# schematic.net
KiCad netlist of a schematic drawn in EasyEDA
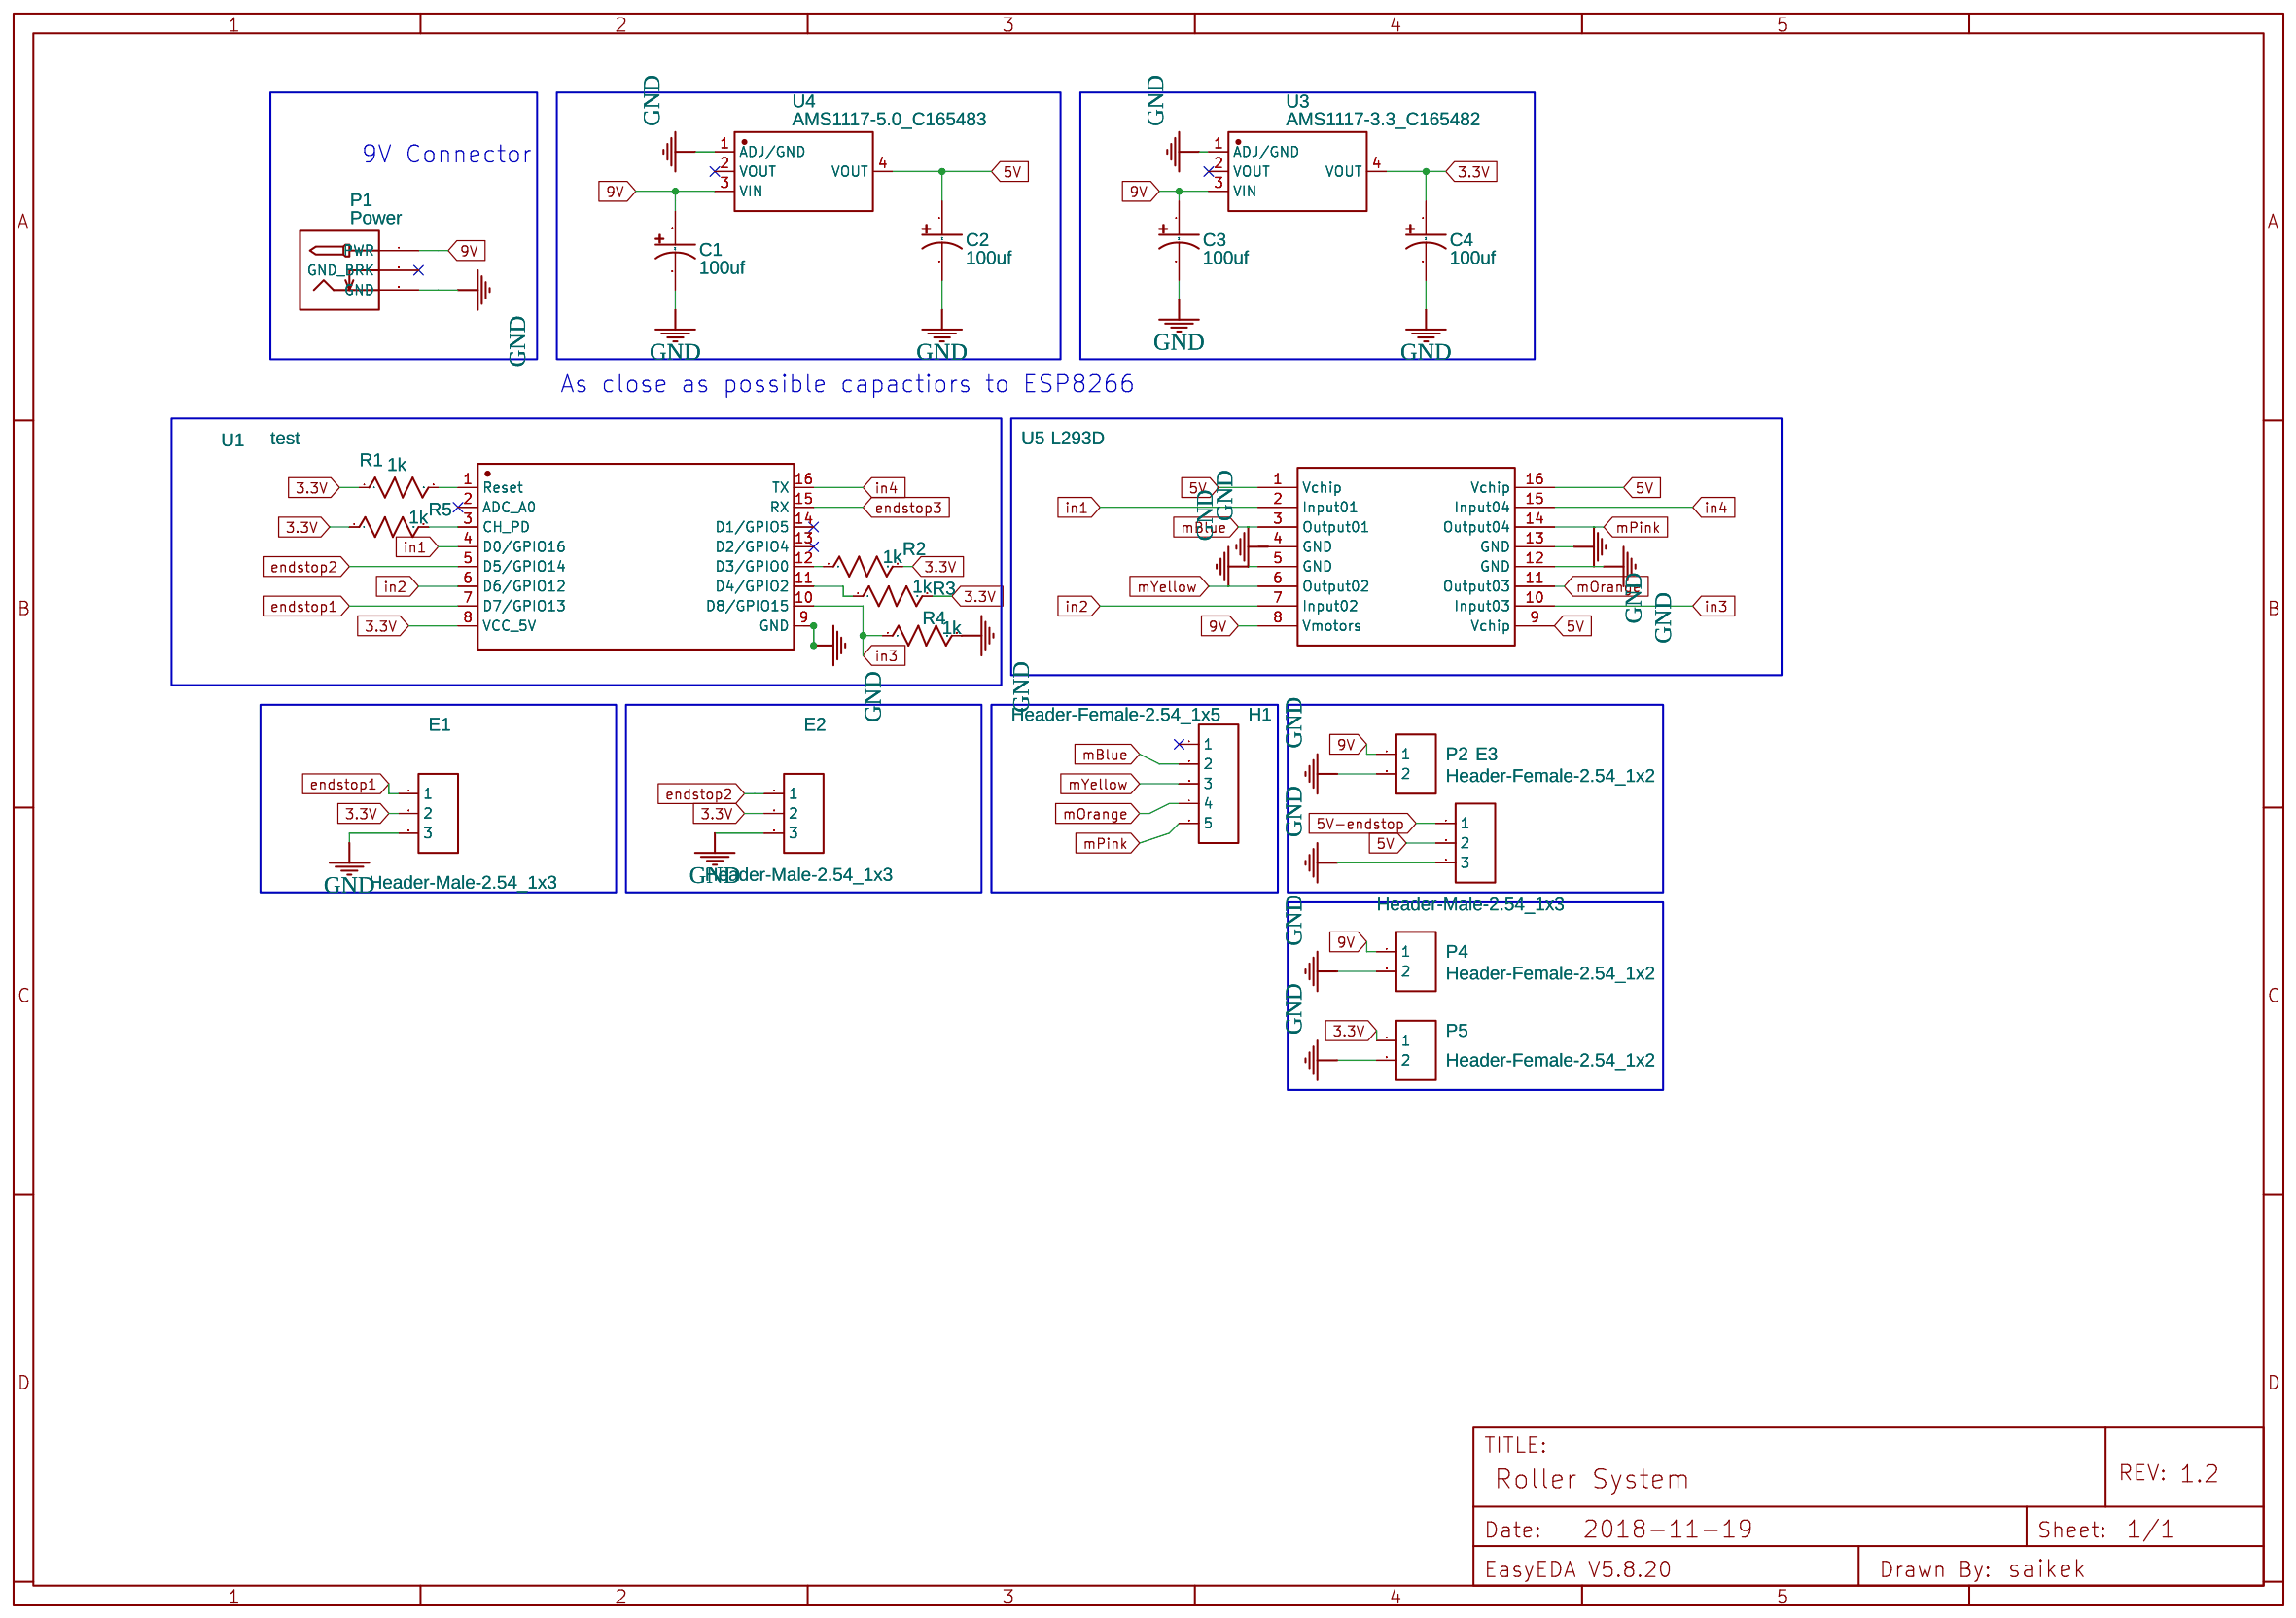
[diagram p0: schematic sheet]

(export (version "E")
  (design (tool "Eeschema 10.0.6"))
  (components
    (comp (ref "C1")
      (value "100uf")
      (fields (field (name "BOM_Manufacturer Part") "?"))
      (libsource (lib "") (part "Cap_Electrolytic(TH)_D3.0XF1.5_US"))
    )
    (comp (ref "C2")
      (value "100uf")
      (fields (field (name "BOM_Manufacturer Part") "?"))
      (libsource (lib "") (part "Cap_Electrolytic(TH)_D3.0XF1.5_US"))
    )
    (comp (ref "C3")
      (value "100uf")
      (fields (field (name "BOM_Manufacturer Part") "?"))
      (libsource (lib "") (part "Cap_Electrolytic(TH)_D3.0XF1.5_US"))
    )
    (comp (ref "C4")
      (value "100uf")
      (fields (field (name "BOM_Manufacturer Part") "?"))
      (libsource (lib "") (part "Cap_Electrolytic(TH)_D3.0XF1.5_US"))
    )
    (comp (ref "E1")
      (value "Header-Male-2.54_1x3")
      (fields
        (field (name "BOM_Manufacturer Part") "Header2.54mm 1*3P")
        (field (name "BOM_Supplier Part") "C49257")
      )
      (libsource (lib "") (part "Unknown_205_405"))
    )
    (comp (ref "E2")
      (value "Header-Male-2.54_1x3")
      (fields
        (field (name "BOM_Manufacturer Part") "Header2.54mm 1*3P")
        (field (name "BOM_Supplier Part") "C49257")
      )
      (libsource (lib "") (part "Unknown_390_405"))
    )
    (comp (ref "E3")
      (value "Header-Male-2.54_1x3")
      (fields
        (field (name "BOM_Manufacturer Part") "Header2.54mm 1*3P")
        (field (name "BOM_Supplier Part") "C49257")
      )
      (libsource (lib "") (part "Unknown_730_420"))
    )
    (comp (ref "H1")
      (value "Header-Female-2.54_1x5")
      (fields
        (field (name "BOM_Manufacturer Part") "2.54mm 1*5p Female header")
        (field (name "BOM_Supplier Part") "C50950")
      )
      (libsource (lib "") (part "Unknown_605_390"))
    )
    (comp (ref "P1")
      (value "Power")
      (fields
        (field (name "BOM_Manufacturer Part") "DC005-2.1MM")
        (field (name "BOM_Supplier Part") "C68942")
      )
      (libsource (lib "") (part "Unknown_175_130"))
    )
    (comp (ref "P2")
      (value "Header-Female-2.54_1x2")
      (fields
        (field (name "BOM_Manufacturer Part") "2.54-1*2PFemale")
        (field (name "BOM_Supplier Part") "C49661")
      )
      (libsource (lib "") (part "Unknown_705_380"))
    )
    (comp (ref "P4")
      (value "Header-Female-2.54_1x2")
      (fields
        (field (name "BOM_Manufacturer Part") "2.54-1*2PFemale")
        (field (name "BOM_Supplier Part") "C49661")
      )
      (libsource (lib "") (part "Unknown_705_480"))
    )
    (comp (ref "P5")
      (value "Header-Female-2.54_1x2")
      (fields
        (field (name "BOM_Manufacturer Part") "2.54-1*2PFemale")
        (field (name "BOM_Supplier Part") "C49661")
      )
      (libsource (lib "") (part "Unknown_705_525"))
    )
    (comp (ref "R1")
      (value "1k")
      (fields (field (name "BOM_Manufacturer Part") "?"))
      (libsource (lib "") (part "Res_0805(1/8W)_US"))
    )
    (comp (ref "R2")
      (value "1k")
      (fields (field (name "BOM_Manufacturer Part") "?"))
      (libsource (lib "") (part "Res_0805(1/8W)_US"))
    )
    (comp (ref "R3")
      (value "1k")
      (fields (field (name "BOM_Manufacturer Part") "?"))
      (libsource (lib "") (part "Res_0805(1/8W)_US"))
    )
    (comp (ref "R4")
      (value "1k")
      (fields (field (name "BOM_Manufacturer Part") "?"))
      (libsource (lib "") (part "Res_0805(1/8W)_US"))
    )
    (comp (ref "R5")
      (value "1k")
      (fields (field (name "BOM_Manufacturer Part") "?"))
      (libsource (lib "") (part "Res_0805(1/8W)_US"))
    )
    (comp (ref "U1")
      (value "test")
      (fields (field (name "BOM_Manufacturer Part") "?"))
      (libsource (lib "") (part "Unknown_315_230"))
    )
    (comp (ref "U3")
      (value "AMS1117-3.3_C165482")
      (fields
        (field (name "BOM_Manufacturer Part") "AMS1117-3.3")
        (field (name "BOM_Supplier Part") "C165482")
      )
      (libsource (lib "") (part "Unknown_645_80"))
    )
    (comp (ref "U4")
      (value "AMS1117-5.0_C165483")
      (fields
        (field (name "BOM_Manufacturer Part") "AMS1117-5.0")
        (field (name "BOM_Supplier Part") "C165483")
      )
      (libsource (lib "") (part "Unknown_405_80"))
    )
    (comp (ref "U5")
      (value "L293D")
      (fields (field (name "BOM_Supplier Part") "C12340"))
      (libsource (lib "") (part "Unknown_650_320"))
    )
  )
  (nets
    (net (code "1") (name "3.3V") (class "Default")
      (node (ref "C4") (pin "1") (pinfunction "1_1") (pintype "unspecified"))
      (node (ref "E1") (pin "2") (pinfunction "2_2") (pintype "input"))
      (node (ref "E2") (pin "2") (pinfunction "2_2") (pintype "input"))
      (node (ref "P5") (pin "1") (pinfunction "1_1") (pintype "input"))
      (node (ref "R1") (pin "1") (pinfunction "1_1") (pintype "unspecified"))
      (node (ref "R2") (pin "2") (pinfunction "2_2") (pintype "unspecified"))
      (node (ref "R3") (pin "2") (pinfunction "2_2") (pintype "unspecified"))
      (node (ref "R5") (pin "1") (pinfunction "1_1") (pintype "unspecified"))
      (node (ref "U1") (pin "8") (pinfunction "VCC_5V_8") (pintype "passive"))
      (node (ref "U3") (pin "4") (pinfunction "VOUT_4") (pintype "unspecified"))
    )
    (net (code "2") (name "5V") (class "Default")
      (node (ref "C2") (pin "1") (pinfunction "1_1") (pintype "unspecified"))
      (node (ref "E3") (pin "2") (pinfunction "2_2") (pintype "input"))
      (node (ref "U4") (pin "4") (pinfunction "VOUT_4") (pintype "unspecified"))
      (node (ref "U5") (pin "1") (pinfunction "Vchip_1") (pintype "unspecified"))
      (node (ref "U5") (pin "16") (pinfunction "Vchip_16") (pintype "unspecified"))
      (node (ref "U5") (pin "9") (pinfunction "Vchip_9") (pintype "unspecified"))
    )
    (net (code "3") (name "5V-endstop") (class "Default")
      (node (ref "E3") (pin "1") (pinfunction "1_1") (pintype "input"))
    )
    (net (code "4") (name "9V") (class "Default")
      (node (ref "C1") (pin "1") (pinfunction "1_1") (pintype "unspecified"))
      (node (ref "C3") (pin "1") (pinfunction "1_1") (pintype "unspecified"))
      (node (ref "P1") (pin "1") (pinfunction "PWR_1") (pintype "unspecified"))
      (node (ref "P2") (pin "1") (pinfunction "1_1") (pintype "input"))
      (node (ref "P4") (pin "1") (pinfunction "1_1") (pintype "input"))
      (node (ref "U3") (pin "3") (pinfunction "VIN_3") (pintype "unspecified"))
      (node (ref "U4") (pin "3") (pinfunction "VIN_3") (pintype "unspecified"))
      (node (ref "U5") (pin "8") (pinfunction "Vmotors_8") (pintype "unspecified"))
    )
    (net (code "5") (name "GND") (class "Default")
      (node (ref "C1") (pin "2") (pinfunction "2_2") (pintype "unspecified"))
      (node (ref "C2") (pin "2") (pinfunction "2_2") (pintype "unspecified"))
      (node (ref "C3") (pin "2") (pinfunction "2_2") (pintype "unspecified"))
      (node (ref "C4") (pin "2") (pinfunction "2_2") (pintype "unspecified"))
      (node (ref "E1") (pin "3") (pinfunction "3_3") (pintype "input"))
      (node (ref "E2") (pin "3") (pinfunction "3_3") (pintype "input"))
      (node (ref "E3") (pin "3") (pinfunction "3_3") (pintype "input"))
      (node (ref "P1") (pin "2") (pinfunction "GND_2") (pintype "unspecified"))
      (node (ref "P2") (pin "2") (pinfunction "2_2") (pintype "input"))
      (node (ref "P4") (pin "2") (pinfunction "2_2") (pintype "input"))
      (node (ref "P5") (pin "2") (pinfunction "2_2") (pintype "input"))
      (node (ref "R4") (pin "2") (pinfunction "2_2") (pintype "unspecified"))
      (node (ref "U1") (pin "9") (pinfunction "GND_9") (pintype "passive"))
      (node (ref "U3") (pin "1") (pinfunction "ADJ/GND_1") (pintype "unspecified"))
      (node (ref "U4") (pin "1") (pinfunction "ADJ/GND_1") (pintype "unspecified"))
      (node (ref "U5") (pin "12") (pinfunction "GND_12") (pintype "unspecified"))
      (node (ref "U5") (pin "13") (pinfunction "GND_13") (pintype "unspecified"))
      (node (ref "U5") (pin "4") (pinfunction "GND_4") (pintype "unspecified"))
      (node (ref "U5") (pin "5") (pinfunction "GND_5") (pintype "unspecified"))
    )
    (net (code "6") (name "Net-(U1-CH_PD)") (class "Default")
      (node (ref "R5") (pin "2") (pinfunction "2_2") (pintype "unspecified"))
      (node (ref "U1") (pin "3") (pinfunction "CH_PD_3") (pintype "unspecified"))
    )
    (net (code "7") (name "Net-(U1-D3{slash}GPIO0)") (class "Default")
      (node (ref "R2") (pin "1") (pinfunction "1_1") (pintype "unspecified"))
      (node (ref "U1") (pin "12") (pinfunction "D3/GPIO0_12") (pintype "unspecified"))
    )
    (net (code "8") (name "Net-(U1-D4{slash}GPIO2)") (class "Default")
      (node (ref "R3") (pin "1") (pinfunction "1_1") (pintype "unspecified"))
      (node (ref "U1") (pin "11") (pinfunction "D4/GPIO2_11") (pintype "unspecified"))
    )
    (net (code "9") (name "Net-(U1-Reset)") (class "Default")
      (node (ref "R1") (pin "2") (pinfunction "2_2") (pintype "unspecified"))
      (node (ref "U1") (pin "1") (pinfunction "Reset_1") (pintype "unspecified"))
    )
    (net (code "10") (name "endstop1") (class "Default")
      (node (ref "E1") (pin "1") (pinfunction "1_1") (pintype "input"))
      (node (ref "U1") (pin "7") (pinfunction "D7/GPIO13_7") (pintype "unspecified"))
    )
    (net (code "11") (name "endstop2") (class "Default")
      (node (ref "E2") (pin "1") (pinfunction "1_1") (pintype "input"))
      (node (ref "U1") (pin "5") (pinfunction "D5/GPIO14_5") (pintype "unspecified"))
    )
    (net (code "12") (name "endstop3") (class "Default")
      (node (ref "U1") (pin "15") (pinfunction "RX_15") (pintype "unspecified"))
    )
    (net (code "13") (name "in1") (class "Default")
      (node (ref "U1") (pin "4") (pinfunction "D0/GPIO16_4") (pintype "unspecified"))
      (node (ref "U5") (pin "2") (pinfunction "Input01_2") (pintype "unspecified"))
    )
    (net (code "14") (name "in2") (class "Default")
      (node (ref "U1") (pin "6") (pinfunction "D6/GPIO12_6") (pintype "unspecified"))
      (node (ref "U5") (pin "7") (pinfunction "Input02_7") (pintype "unspecified"))
    )
    (net (code "15") (name "in3") (class "Default")
      (node (ref "R4") (pin "1") (pinfunction "1_1") (pintype "unspecified"))
      (node (ref "U1") (pin "10") (pinfunction "D8/GPIO15_10") (pintype "unspecified"))
      (node (ref "U5") (pin "10") (pinfunction "Input03_10") (pintype "unspecified"))
    )
    (net (code "16") (name "in4") (class "Default")
      (node (ref "U1") (pin "16") (pinfunction "TX_16") (pintype "unspecified"))
      (node (ref "U5") (pin "15") (pinfunction "Input04_15") (pintype "unspecified"))
    )
    (net (code "17") (name "mBlue") (class "Default")
      (node (ref "H1") (pin "2") (pinfunction "2_2") (pintype "input"))
      (node (ref "U5") (pin "3") (pinfunction "Output01_3") (pintype "unspecified"))
    )
    (net (code "18") (name "mOrange") (class "Default")
      (node (ref "H1") (pin "4") (pinfunction "4_4") (pintype "input"))
      (node (ref "U5") (pin "11") (pinfunction "Output03_11") (pintype "unspecified"))
    )
    (net (code "19") (name "mPink") (class "Default")
      (node (ref "H1") (pin "5") (pinfunction "5_5") (pintype "input"))
      (node (ref "U5") (pin "14") (pinfunction "Output04_14") (pintype "unspecified"))
    )
    (net (code "20") (name "mYellow") (class "Default")
      (node (ref "H1") (pin "3") (pinfunction "3_3") (pintype "input"))
      (node (ref "U5") (pin "6") (pinfunction "Output02_6") (pintype "unspecified"))
    )
    (net (code "21") (name "unconnected-(H1-Pad1)") (class "Default")
      (node (ref "H1") (pin "1") (pinfunction "1_1") (pintype "input+no_connect"))
    )
    (net (code "22") (name "unconnected-(P1-GND_BRK-Pad3)") (class "Default")
      (node (ref "P1") (pin "3") (pinfunction "GND_BRK_3") (pintype "unspecified+no_connect"))
    )
    (net (code "23") (name "unconnected-(U1-ADC_A0-Pad2)") (class "Default")
      (node (ref "U1") (pin "2") (pinfunction "ADC_A0_2") (pintype "unspecified+no_connect"))
    )
    (net (code "24") (name "unconnected-(U1-D1{slash}GPIO5-Pad14)") (class "Default")
      (node (ref "U1") (pin "14") (pinfunction "D1/GPIO5_14") (pintype "unspecified+no_connect"))
    )
    (net (code "25") (name "unconnected-(U1-D2{slash}GPIO4-Pad13)") (class "Default")
      (node (ref "U1") (pin "13") (pinfunction "D2/GPIO4_13") (pintype "unspecified+no_connect"))
    )
    (net (code "26") (name "unconnected-(U3-VOUT-Pad2)") (class "Default")
      (node (ref "U3") (pin "2") (pinfunction "VOUT_2") (pintype "unspecified+no_connect"))
    )
    (net (code "27") (name "unconnected-(U4-VOUT-Pad2)") (class "Default")
      (node (ref "U4") (pin "2") (pinfunction "VOUT_2") (pintype "unspecified+no_connect"))
    )
  )
)
